# Plug_Base.net
KiCad netlist of a schematic drawn in Altium Designer
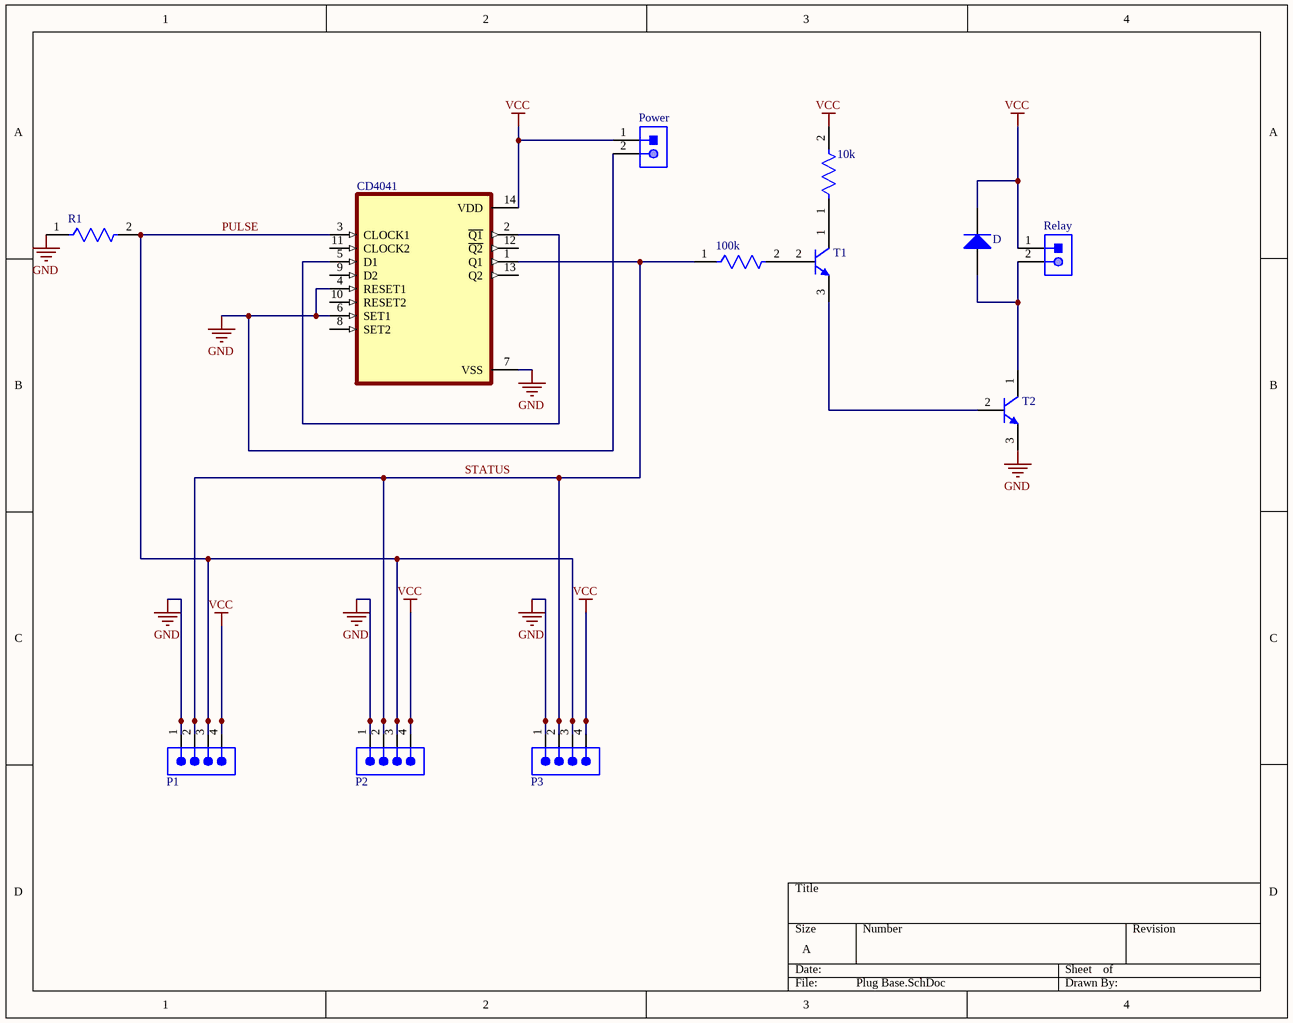
[diagram p0: Plug Base.SchDoc]

(export (version "E")
  (design (tool "Eeschema 10.0.6"))
  (components
    (comp (ref "10k")
      (value "CFR-25JB-52-10R")
      (footprint "FP-CFR-25-MFG")
      (description "RES 10 OHM 1/4W 5% AXIAL")
      (fields (field (name "TOLERANCE") "5%"))
      (libsource (lib "Altium Content Vault") (part "1029c3af85768c4190bb7ad29bc67b5"))
    )
    (comp (ref "100k")
      (value "CFR-25JB-52-10R")
      (footprint "FP-CFR-25-MFG")
      (description "RES 10 OHM 1/4W 5% AXIAL")
      (fields (field (name "TOLERANCE") "5%"))
      (libsource (lib "Altium Content Vault") (part "1029c3af85768c4190bb7ad29bc67b5"))
    )
    (comp (ref "CD4041")
      (value "CD4013BEE4")
      (footprint "DIP794W45P254L1969H508Q14")
      (description "CMOS Dual D-Type Flip Flop 14-PDIP -55 to 125")
      (fields (field (name "MF") "Texas Instruments"))
      (libsource (lib "CD4013BEE4") (part "CD4013BEE4"))
    )
    (comp (ref "D")
      (value "1N4001-T")
      (footprint "DIOD-DO-41-P-2_V")
      (description "1.0 A Rectifier, 15 pF, 50 V, -65 to 150 degC, 2-Pin DO-41 Plastic, RoHS, Tape and Reel")
      (fields (field (name "MANUFACTURER") "Diodes Inc"))
      (libsource (lib "Altium Content Vault") (part "DIOD-D-A1K2-2"))
    )
    (comp (ref "P1")
      (value "TSW-104-08-L-S")
      (footprint "SMTC-TSW-104-08-X-S")
      (description "0.025\" SQ Post Header, Through-hole, Vertical, -55 to 125 degC, 2.54 mm Pitch, 4-Pin, Male, RoHS")
      (fields (field (name "MANUFACTURER") "Samtec"))
      (libsource (lib "Altium Content Vault") (part "SMTC-TSW-104-08-X-S"))
    )
    (comp (ref "P2")
      (value "TSW-104-08-L-S")
      (footprint "SMTC-TSW-104-08-X-S")
      (description "0.025\" SQ Post Header, Through-hole, Vertical, -55 to 125 degC, 2.54 mm Pitch, 4-Pin, Male, RoHS")
      (fields (field (name "MANUFACTURER") "Samtec"))
      (libsource (lib "Altium Content Vault") (part "SMTC-TSW-104-08-X-S"))
    )
    (comp (ref "P3")
      (value "TSW-104-08-L-S")
      (footprint "SMTC-TSW-104-08-X-S")
      (description "0.025\" SQ Post Header, Through-hole, Vertical, -55 to 125 degC, 2.54 mm Pitch, 4-Pin, Male, RoHS")
      (fields (field (name "MANUFACTURER") "Samtec"))
      (libsource (lib "Altium Content Vault") (part "SMTC-TSW-104-08-X-S"))
    )
    (comp (ref "Power")
      (value "61300211121")
      (footprint "61300211121")
      (description "THT Vertical Pin Header WR-PHD, Pitch 2.54 mm, Single Row, 2 pins")
      (fields (field (name "MANUFACTURER") "Wurth Elektronik") (field (name "PUBLISHER") "WurthElektronik"))
      (libsource (lib "Altium Content Vault") (part "WE-CN-1P-M-R2"))
    )
    (comp (ref "R1")
      (value "CFR-25JB-52-10R")
      (footprint "FP-CFR-25-MFG")
      (description "RES 10 OHM 1/4W 5% AXIAL")
      (fields (field (name "TOLERANCE") "5%"))
      (libsource (lib "Altium Content Vault") (part "1029c3af85768c4190bb7ad29bc67b5"))
    )
    (comp (ref "Relay")
      (value "61300211121")
      (footprint "61300211121")
      (description "THT Vertical Pin Header WR-PHD, Pitch 2.54 mm, Single Row, 2 pins")
      (fields (field (name "MANUFACTURER") "Wurth Elektronik") (field (name "PUBLISHER") "WurthElektronik"))
      (libsource (lib "Altium Content Vault") (part "WE-CN-1P-M-R2"))
    )
    (comp (ref "T1")
      (value "BC337-25ZL1G")
      (footprint "ONSC-TO-92-3-29-11_AM_BL")
      (description "Amplifier Transistor, NPN Silicon, 3-Pin TO-92, Pb-Free, Ammo Box")
      (fields (field (name "MANUFACTURER") "On Semiconductor"))
      (libsource (lib "Altium Content Vault") (part "ONSC-NPN-C1B2E3-3"))
    )
    (comp (ref "T2")
      (value "BC337-25ZL1G")
      (footprint "ONSC-TO-92-3-29-11_AM_BL")
      (description "Amplifier Transistor, NPN Silicon, 3-Pin TO-92, Pb-Free, Ammo Box")
      (fields (field (name "MANUFACTURER") "On Semiconductor"))
      (libsource (lib "Altium Content Vault") (part "ONSC-NPN-C1B2E3-3"))
    )
  )
  (nets
    (net (code "1") (name "/PULSE") (class "Default")
      (node (ref "CD4041") (pin "3") (pinfunction "CLOCK1_3") (pintype "input"))
      (node (ref "P1") (pin "3") (pinfunction "3_3") (pintype "passive"))
      (node (ref "P2") (pin "3") (pinfunction "3_3") (pintype "passive"))
      (node (ref "P3") (pin "3") (pinfunction "3_3") (pintype "passive"))
      (node (ref "R1") (pin "2") (pinfunction "2_2") (pintype "passive"))
    )
    (net (code "2") (name "/STATUS") (class "Default")
      (node (ref "100k") (pin "1") (pinfunction "1_1") (pintype "passive"))
      (node (ref "CD4041") (pin "1") (pinfunction "Q1_1") (pintype "output"))
      (node (ref "P1") (pin "2") (pinfunction "2_2") (pintype "passive"))
      (node (ref "P2") (pin "2") (pinfunction "2_2") (pintype "passive"))
      (node (ref "P3") (pin "2") (pinfunction "2_2") (pintype "passive"))
    )
    (net (code "3") (name "GND") (class "Default")
      (node (ref "CD4041") (pin "4") (pinfunction "RESET1_4") (pintype "input"))
      (node (ref "CD4041") (pin "6") (pinfunction "SET1_6") (pintype "input"))
      (node (ref "CD4041") (pin "7") (pinfunction "VSS_7") (pintype "power_in"))
      (node (ref "P1") (pin "1") (pinfunction "1_1") (pintype "passive"))
      (node (ref "P2") (pin "1") (pinfunction "1_1") (pintype "passive"))
      (node (ref "P3") (pin "1") (pinfunction "1_1") (pintype "passive"))
      (node (ref "Power") (pin "2") (pinfunction "2_2") (pintype "passive"))
      (node (ref "R1") (pin "1") (pinfunction "1_1") (pintype "passive"))
      (node (ref "T2") (pin "3") (pinfunction "E_3") (pintype "passive"))
    )
    (net (code "4") (name "Net-(CD4041-D1)") (class "Default")
      (node (ref "CD4041") (pin "2") (pinfunction "~{Q1}_2") (pintype "output"))
      (node (ref "CD4041") (pin "5") (pinfunction "D1_5") (pintype "input"))
    )
    (net (code "5") (name "Net-(D-A)") (class "Default")
      (node (ref "D") (pin "1") (pinfunction "A_1") (pintype "passive"))
      (node (ref "Relay") (pin "2") (pinfunction "2_2") (pintype "passive"))
      (node (ref "T2") (pin "1") (pinfunction "C_1") (pintype "passive"))
    )
    (net (code "6") (name "Net-(T1-B)") (class "Default")
      (node (ref "100k") (pin "2") (pinfunction "2_2") (pintype "passive"))
      (node (ref "T1") (pin "2") (pinfunction "B_2") (pintype "passive"))
    )
    (net (code "7") (name "Net-(T1-C)") (class "Default")
      (node (ref "10k") (pin "1") (pinfunction "1_1") (pintype "passive"))
      (node (ref "T1") (pin "1") (pinfunction "C_1") (pintype "passive"))
    )
    (net (code "8") (name "Net-(T1-E)") (class "Default")
      (node (ref "T1") (pin "3") (pinfunction "E_3") (pintype "passive"))
      (node (ref "T2") (pin "2") (pinfunction "B_2") (pintype "passive"))
    )
    (net (code "9") (name "VCC") (class "Default")
      (node (ref "10k") (pin "2") (pinfunction "2_2") (pintype "passive"))
      (node (ref "CD4041") (pin "14") (pinfunction "VDD_14") (pintype "power_in"))
      (node (ref "D") (pin "2") (pinfunction "K_2") (pintype "passive"))
      (node (ref "P1") (pin "4") (pinfunction "4_4") (pintype "passive"))
      (node (ref "P2") (pin "4") (pinfunction "4_4") (pintype "passive"))
      (node (ref "P3") (pin "4") (pinfunction "4_4") (pintype "passive"))
      (node (ref "Power") (pin "1") (pinfunction "1_1") (pintype "passive"))
      (node (ref "Relay") (pin "1") (pinfunction "1_1") (pintype "passive"))
    )
    (net (code "10") (name "unconnected-(CD4041-CLOCK2-Pad11)") (class "Default")
      (node (ref "CD4041") (pin "11") (pinfunction "CLOCK2_11") (pintype "input"))
    )
    (net (code "11") (name "unconnected-(CD4041-D2-Pad9)") (class "Default")
      (node (ref "CD4041") (pin "9") (pinfunction "D2_9") (pintype "input"))
    )
    (net (code "12") (name "unconnected-(CD4041-Q2-Pad13)") (class "Default")
      (node (ref "CD4041") (pin "13") (pinfunction "Q2_13") (pintype "output"))
    )
    (net (code "13") (name "unconnected-(CD4041-RESET2-Pad10)") (class "Default")
      (node (ref "CD4041") (pin "10") (pinfunction "RESET2_10") (pintype "input"))
    )
    (net (code "14") (name "unconnected-(CD4041-SET2-Pad8)") (class "Default")
      (node (ref "CD4041") (pin "8") (pinfunction "SET2_8") (pintype "input"))
    )
    (net (code "15") (name "unconnected-(CD4041-~{Q2}-Pad12)") (class "Default")
      (node (ref "CD4041") (pin "12") (pinfunction "~{Q2}_12") (pintype "output"))
    )
  )
)
